# mic_amp.net
KiCad netlist of a schematic drawn in Altium Designer
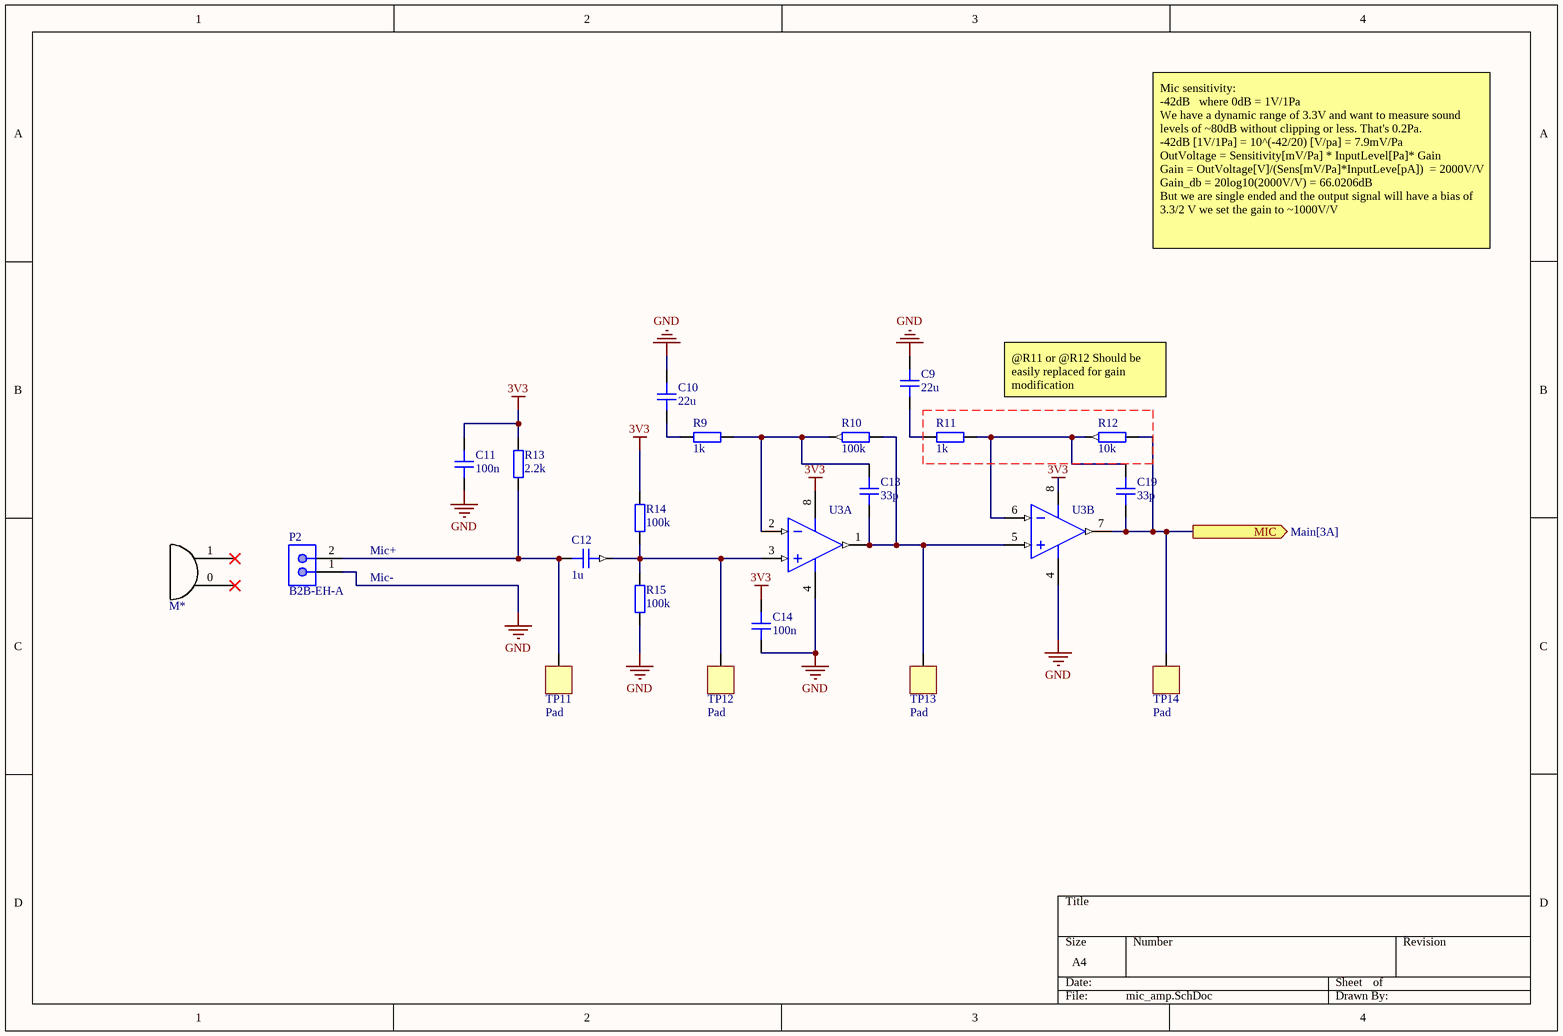
[diagram p0: mic_amp.SchDoc]

(export (version "E")
  (design (tool "Eeschema 10.0.6"))
  (components
    (comp (ref "C9")
      (value "22u")
      (footprint "CAP_0603")
      (description "Capacitor SMD 0603, X7R, 10V")
      (libsource (lib "Schematic-Lib-PhilsLab") (part "CAP_0603"))
    )
    (comp (ref "C10")
      (value "22u")
      (footprint "CAP_0603")
      (description "Capacitor SMD 0603, X7R, 10V")
      (libsource (lib "Schematic-Lib-PhilsLab") (part "CAP_0603"))
    )
    (comp (ref "C11")
      (value "100n")
      (footprint "CAP_0603")
      (description "Capacitor SMD 0603, X7R, 10V")
      (libsource (lib "Schematic-Lib-PhilsLab") (part "CAP_0603"))
    )
    (comp (ref "C12")
      (value "1u")
      (footprint "CAP_0603")
      (description "Capacitor SMD 0603, X7R, 10V")
      (libsource (lib "Schematic-Lib-PhilsLab") (part "CAP_0603"))
    )
    (comp (ref "C13")
      (value "33p")
      (footprint "CAP_0603")
      (description "Capacitor SMD 0603, X7R, 10V")
      (libsource (lib "Schematic-Lib-PhilsLab") (part "CAP_0603"))
    )
    (comp (ref "C14")
      (value "100n")
      (footprint "CAP_0603")
      (description "Capacitor SMD 0603, X7R, 10V")
      (libsource (lib "Schematic-Lib-PhilsLab") (part "CAP_0603"))
    )
    (comp (ref "C19")
      (value "33p")
      (footprint "CAP_0603")
      (description "Capacitor SMD 0603, X7R, 10V")
      (libsource (lib "Schematic-Lib-PhilsLab") (part "CAP_0603"))
    )
    (comp (ref "M*")
      (value "LD-MC-0905P")
      (description "Microphone, electret")
      (libsource (lib "Schematic-Lib-PhilsLab") (part "LD-MC-0905P"))
    )
    (comp (ref "P2")
      (value "B2B-EH-A")
      (footprint "JST-B2B-EH-A_V")
      (fields (field (name "MANUFACTURER") "JST"))
      (libsource (lib "Altium Content Vault") (part "CN-1P-M-R2"))
    )
    (comp (ref "R9")
      (value "1k")
      (footprint "RES_0603")
      (description "Resistor SMD 0603")
      (libsource (lib "Schematic-Lib-PhilsLab") (part "RES_0603"))
    )
    (comp (ref "R10")
      (value "100k")
      (footprint "RES_0603")
      (description "Resistor SMD 0603")
      (libsource (lib "Schematic-Lib-PhilsLab") (part "RES_0603"))
    )
    (comp (ref "R11")
      (value "1k")
      (footprint "RES_0603")
      (description "Resistor SMD 0603")
      (libsource (lib "Schematic-Lib-PhilsLab") (part "RES_0603"))
    )
    (comp (ref "R12")
      (value "10k")
      (footprint "RES_0603")
      (description "Resistor SMD 0603")
      (libsource (lib "Schematic-Lib-PhilsLab") (part "RES_0603"))
    )
    (comp (ref "R13")
      (value "2.2k")
      (footprint "RES_0603")
      (description "Resistor SMD 0603")
      (libsource (lib "Schematic-Lib-PhilsLab") (part "RES_0603"))
    )
    (comp (ref "R14")
      (value "100k")
      (footprint "RES_0603")
      (description "Resistor SMD 0603")
      (libsource (lib "Schematic-Lib-PhilsLab") (part "RES_0603"))
    )
    (comp (ref "R15")
      (value "100k")
      (footprint "RES_0603")
      (description "Resistor SMD 0603")
      (libsource (lib "Schematic-Lib-PhilsLab") (part "RES_0603"))
    )
    (comp (ref "TP11")
      (value "Pad")
      (footprint "PAD_SQ_2MM")
      (description "Test Point Square 2mm")
      (libsource (lib "Schematic-Lib-PhilsLab") (part "PAD_SQ_2MM"))
    )
    (comp (ref "TP12")
      (value "Pad")
      (footprint "PAD_SQ_2MM")
      (description "Test Point Square 2mm")
      (libsource (lib "Schematic-Lib-PhilsLab") (part "PAD_SQ_2MM"))
    )
    (comp (ref "TP13")
      (value "Pad")
      (footprint "PAD_SQ_2MM")
      (description "Test Point Square 2mm")
      (libsource (lib "Schematic-Lib-PhilsLab") (part "PAD_SQ_2MM"))
    )
    (comp (ref "TP14")
      (value "Pad")
      (footprint "PAD_SQ_2MM")
      (description "Test Point Square 2mm")
      (libsource (lib "Schematic-Lib-PhilsLab") (part "PAD_SQ_2MM"))
    )
    (comp (ref "U3")
      (value "AD8602ARZ-REEL7")
      (footprint "ADI-R-8_M")
      (fields (field (name "MANUFACTURER") "Analog Devices") (field (name "GENERIC PART NUMBER") "AD8602"))
      (libsource (lib "Altium Content Vault") (part "ADI-OP29X-R-8"))
    )
  )
  (nets
    (net (code "1") (name "/MIC") (class "Default")
      (node (ref "C19") (pin "1") (pinfunction "1_1") (pintype "passive"))
      (node (ref "R12") (pin "1") (pinfunction "1_1") (pintype "passive"))
      (node (ref "TP14") (pin "1") (pinfunction "1_1") (pintype "passive"))
      (node (ref "U3") (pin "7") (pinfunction "OUT_B_7") (pintype "output"))
    )
    (net (code "2") (name "3V3") (class "Default")
      (node (ref "C11") (pin "2") (pinfunction "2_2") (pintype "passive"))
      (node (ref "C14") (pin "2") (pinfunction "2_2") (pintype "passive"))
      (node (ref "R13") (pin "2") (pinfunction "2_2") (pintype "passive"))
      (node (ref "R14") (pin "2") (pinfunction "2_2") (pintype "passive"))
      (node (ref "U3") (pin "8") (pinfunction "+V_8") (pintype "power_in"))
    )
    (net (code "3") (name "GND") (class "Default")
      (node (ref "C10") (pin "2") (pinfunction "2_2") (pintype "passive"))
      (node (ref "C11") (pin "1") (pinfunction "1_1") (pintype "passive"))
      (node (ref "C14") (pin "1") (pinfunction "1_1") (pintype "passive"))
      (node (ref "C9") (pin "2") (pinfunction "2_2") (pintype "passive"))
      (node (ref "P2") (pin "1") (pinfunction "1_1") (pintype "passive"))
      (node (ref "R15") (pin "1") (pinfunction "1_1") (pintype "passive"))
      (node (ref "U3") (pin "4") (pinfunction "-V_4") (pintype "power_in"))
    )
    (net (code "4") (name "Net-(C9-Pad1)") (class "Default")
      (node (ref "C9") (pin "1") (pinfunction "1_1") (pintype "passive"))
      (node (ref "R11") (pin "2") (pinfunction "2_2") (pintype "passive"))
    )
    (net (code "5") (name "Net-(C10-Pad1)") (class "Default")
      (node (ref "C10") (pin "1") (pinfunction "1_1") (pintype "passive"))
      (node (ref "R9") (pin "2") (pinfunction "2_2") (pintype "passive"))
    )
    (net (code "6") (name "Net-(C12-Pad2)") (class "Default")
      (node (ref "C12") (pin "2") (pinfunction "2_2") (pintype "passive"))
      (node (ref "P2") (pin "2") (pinfunction "2_2") (pintype "passive"))
      (node (ref "R13") (pin "1") (pinfunction "1_1") (pintype "passive"))
      (node (ref "TP11") (pin "1") (pinfunction "1_1") (pintype "passive"))
    )
    (net (code "7") (name "Net-(U3A-+IN_A)") (class "Default")
      (node (ref "C12") (pin "1") (pinfunction "1_1") (pintype "passive"))
      (node (ref "R14") (pin "1") (pinfunction "1_1") (pintype "passive"))
      (node (ref "R15") (pin "2") (pinfunction "2_2") (pintype "passive"))
      (node (ref "TP12") (pin "1") (pinfunction "1_1") (pintype "passive"))
      (node (ref "U3") (pin "3") (pinfunction "+IN_A_3") (pintype "input"))
    )
    (net (code "8") (name "Net-(U3A--IN_A)") (class "Default")
      (node (ref "C13") (pin "2") (pinfunction "2_2") (pintype "passive"))
      (node (ref "R10") (pin "2") (pinfunction "2_2") (pintype "passive"))
      (node (ref "R9") (pin "1") (pinfunction "1_1") (pintype "passive"))
      (node (ref "U3") (pin "2") (pinfunction "-IN_A_2") (pintype "input"))
    )
    (net (code "9") (name "Net-(U3A-OUT_A)") (class "Default")
      (node (ref "C13") (pin "1") (pinfunction "1_1") (pintype "passive"))
      (node (ref "R10") (pin "1") (pinfunction "1_1") (pintype "passive"))
      (node (ref "TP13") (pin "1") (pinfunction "1_1") (pintype "passive"))
      (node (ref "U3") (pin "1") (pinfunction "OUT_A_1") (pintype "output"))
      (node (ref "U3") (pin "5") (pinfunction "+IN_B_5") (pintype "input"))
    )
    (net (code "10") (name "Net-(U3B--IN_B)") (class "Default")
      (node (ref "C19") (pin "2") (pinfunction "2_2") (pintype "passive"))
      (node (ref "R11") (pin "1") (pinfunction "1_1") (pintype "passive"))
      (node (ref "R12") (pin "2") (pinfunction "2_2") (pintype "passive"))
      (node (ref "U3") (pin "6") (pinfunction "-IN_B_6") (pintype "input"))
    )
    (net (code "11") (name "unconnected-(M*-6-Pad0)") (class "Default")
      (node (ref "M*") (pin "0") (pinfunction "6_0") (pintype "passive+no_connect"))
    )
    (net (code "12") (name "unconnected-(M*-7-Pad1)") (class "Default")
      (node (ref "M*") (pin "1") (pinfunction "7_1") (pintype "passive+no_connect"))
    )
  )
)
